# candle_circuit.net
KiCad netlist of a schematic drawn in EAGLE
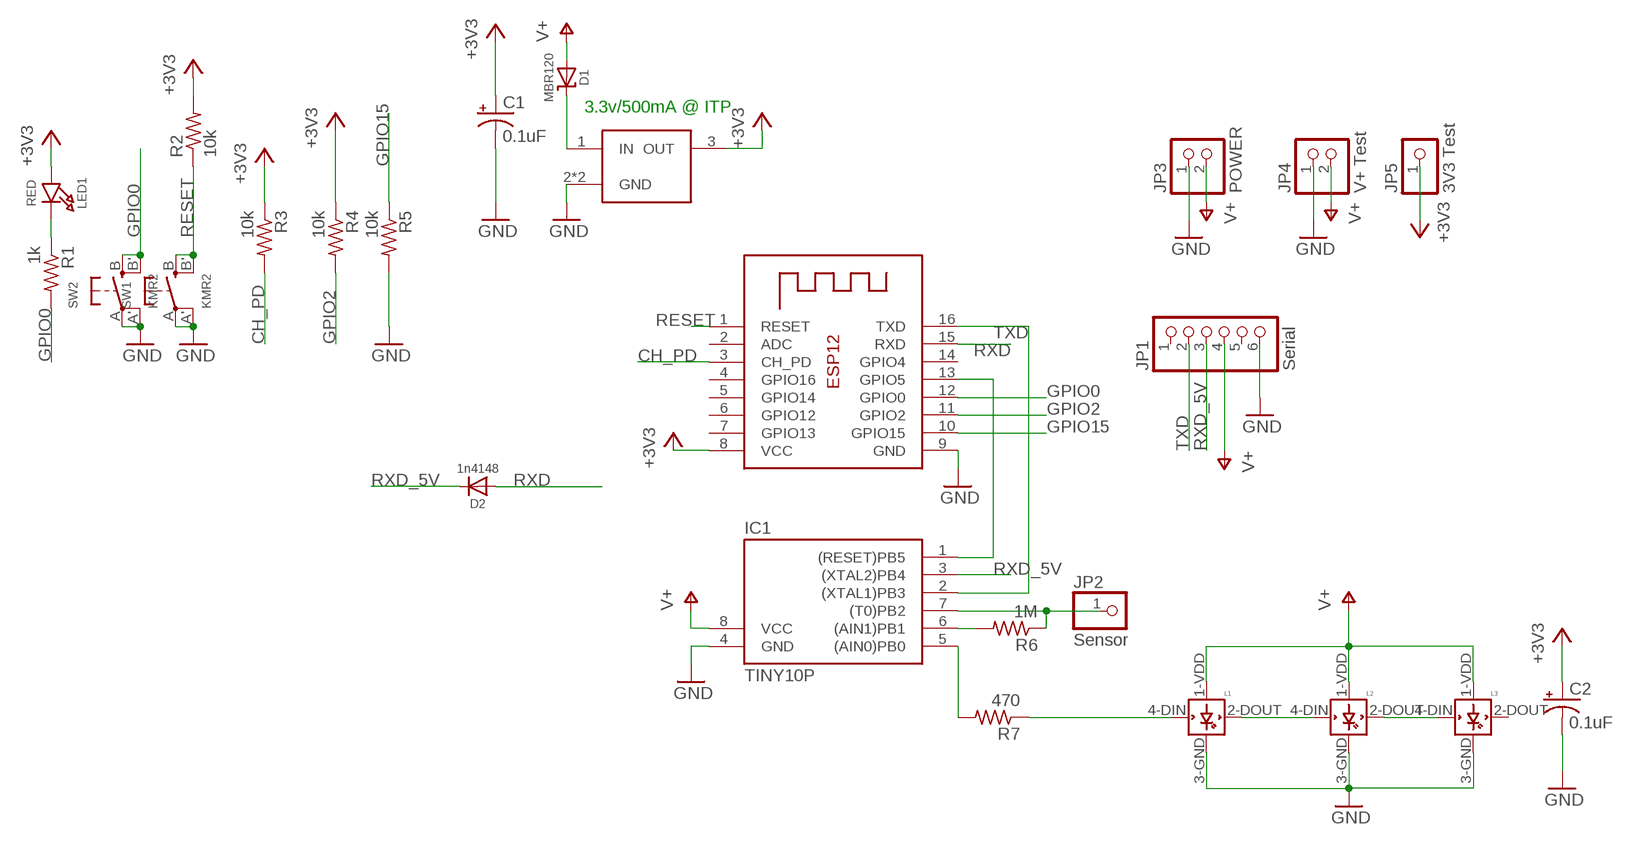
[diagram p0: schematic, sheet 1]

(export (version "E")
  (design (tool "Eeschema 10.0.6"))
  (components
    (comp (ref "C1")
      (value "0.1uF")
      (footprint "eagle-import:PANASONIC_C")
      (libsource (lib "eagle-import") (part "CAP_POLC"))
    )
    (comp (ref "C2")
      (value "0.1uF")
      (footprint "eagle-import:PANASONIC_C")
      (libsource (lib "eagle-import") (part "CAP_POLC"))
    )
    (comp (ref "D1")
      (value "MBR120")
      (footprint "eagle-import:SOD-123")
      (libsource (lib "eagle-import") (part "DIODE-SCHOTTKYSOD-123"))
    )
    (comp (ref "D2")
      (value "1n4148")
      (footprint "eagle-import:SOD-323")
      (libsource (lib "eagle-import") (part "DIODESOD-323"))
    )
    (comp (ref "IC1")
      (value "TINY10P")
      (footprint "eagle-import:DIL08")
      (libsource (lib "eagle-import") (part "TINY10P"))
    )
    (comp (ref "IC2")
      (value "ESP-12")
      (footprint "eagle-import:ESP-12")
      (libsource (lib "eagle-import") (part "ESP-12"))
    )
    (comp (ref "JP1")
      (value "Serial")
      (footprint "eagle-import:1X06_OVAL")
      (libsource (lib "eagle-import") (part "HEADER-1X6"))
    )
    (comp (ref "JP2")
      (value "Sensor")
      (footprint "eagle-import:1X01")
      (libsource (lib "eagle-import") (part "PINHD-1X1"))
    )
    (comp (ref "JP3")
      (value "POWER")
      (footprint "eagle-import:1X02_OVAL")
      (libsource (lib "eagle-import") (part "HEADER-1X2"))
    )
    (comp (ref "JP4")
      (value "V+ Test")
      (footprint "eagle-import:1X02_OVAL")
      (libsource (lib "eagle-import") (part "HEADER-1X2"))
    )
    (comp (ref "JP5")
      (value "3V3 Test")
      (footprint "eagle-import:1X01")
      (libsource (lib "eagle-import") (part "PINHD-1X1"))
    )
    (comp (ref "L1")
      (value "WS2812B")
      (footprint "eagle-import:WS2812B")
      (libsource (lib "eagle-import") (part "WS2812B"))
    )
    (comp (ref "L2")
      (value "WS2812B")
      (footprint "eagle-import:WS2812B")
      (libsource (lib "eagle-import") (part "WS2812B"))
    )
    (comp (ref "L3")
      (value "WS2812B")
      (footprint "eagle-import:WS2812B")
      (libsource (lib "eagle-import") (part "WS2812B"))
    )
    (comp (ref "LED1")
      (value "RED")
      (footprint "eagle-import:CHIPLED_0805_NOOUTLINE")
      (libsource (lib "eagle-import") (part "LED0805_NOOUTLINE"))
    )
    (comp (ref "R1")
      (value "1k")
      (footprint "eagle-import:R0603")
      (libsource (lib "eagle-import") (part "R-US_R0603"))
    )
    (comp (ref "R2")
      (value "10k")
      (footprint "eagle-import:R0603")
      (libsource (lib "eagle-import") (part "R-US_R0603"))
    )
    (comp (ref "R3")
      (value "10k")
      (footprint "eagle-import:R0603")
      (libsource (lib "eagle-import") (part "R-US_R0603"))
    )
    (comp (ref "R4")
      (value "10k")
      (footprint "eagle-import:R0603")
      (libsource (lib "eagle-import") (part "R-US_R0603"))
    )
    (comp (ref "R5")
      (value "10k")
      (footprint "eagle-import:R0603")
      (libsource (lib "eagle-import") (part "R-US_R0603"))
    )
    (comp (ref "R6")
      (value "1M")
      (footprint "eagle-import:R0603")
      (libsource (lib "eagle-import") (part "R-US_R0603"))
    )
    (comp (ref "R7")
      (value "470")
      (footprint "eagle-import:R0603")
      (libsource (lib "eagle-import") (part "R-US_R0603"))
    )
    (comp (ref "SW1")
      (value "KMR2")
      (footprint "eagle-import:BTN_KMR2_4.6X2.8")
      (libsource (lib "eagle-import") (part "SWITCH_TACT_SMT4.6X2.8"))
    )
    (comp (ref "SW2")
      (value "KMR2")
      (footprint "eagle-import:BTN_KMR2_4.6X2.8")
      (libsource (lib "eagle-import") (part "SWITCH_TACT_SMT4.6X2.8"))
    )
    (comp (ref "U1")
      (value "REGULATOR3.3V-UA78M33CDCYR")
      (footprint "eagle-import:SOT223")
      (libsource (lib "eagle-import") (part "REGULATOR3.3V-UA78M33CDCYR"))
    )
  )
  (nets
    (net (code "1") (name "+3V3") (class "Default")
      (node (ref "C1") (pin "+") (pinfunction "+_+") (pintype "passive"))
      (node (ref "C2") (pin "+") (pinfunction "+_+") (pintype "passive"))
      (node (ref "IC2") (pin "8") (pinfunction "VCC_8") (pintype "power_in"))
      (node (ref "JP5") (pin "1") (pinfunction "1_1") (pintype "passive"))
      (node (ref "LED1") (pin "A") (pinfunction "A_A") (pintype "passive"))
      (node (ref "R2") (pin "2") (pinfunction "2_2") (pintype "passive"))
      (node (ref "R3") (pin "1") (pinfunction "1_1") (pintype "passive"))
      (node (ref "R4") (pin "1") (pinfunction "1_1") (pintype "passive"))
      (node (ref "U1") (pin "3") (pinfunction "OUT_3") (pintype "bidirectional"))
    )
    (net (code "2") (name "/CH_PD") (class "Default")
      (node (ref "IC2") (pin "3") (pinfunction "CH_PD_3") (pintype "input"))
      (node (ref "R3") (pin "2") (pinfunction "2_2") (pintype "passive"))
    )
    (net (code "3") (name "/GPIO0") (class "Default")
      (node (ref "IC2") (pin "12") (pinfunction "GPIO0_12") (pintype "bidirectional"))
      (node (ref "R1") (pin "2") (pinfunction "2_2") (pintype "passive"))
      (node (ref "SW2") (pin "B") (pinfunction "S_B") (pintype "passive"))
      (node (ref "SW2") (pin "B'") (pinfunction "S1_B'") (pintype "passive"))
    )
    (net (code "4") (name "/GPIO2") (class "Default")
      (node (ref "IC2") (pin "11") (pinfunction "GPIO2_11") (pintype "bidirectional"))
      (node (ref "R4") (pin "2") (pinfunction "2_2") (pintype "passive"))
    )
    (net (code "5") (name "/GPIO15") (class "Default")
      (node (ref "IC2") (pin "10") (pinfunction "GPIO15_10") (pintype "bidirectional"))
      (node (ref "R5") (pin "1") (pinfunction "1_1") (pintype "passive"))
    )
    (net (code "6") (name "/RESET") (class "Default")
      (node (ref "IC2") (pin "1") (pinfunction "RESET_1") (pintype "input"))
      (node (ref "R2") (pin "1") (pinfunction "1_1") (pintype "passive"))
      (node (ref "SW1") (pin "B") (pinfunction "S_B") (pintype "passive"))
      (node (ref "SW1") (pin "B'") (pinfunction "S1_B'") (pintype "passive"))
    )
    (net (code "7") (name "/RXD") (class "Default")
      (node (ref "D2") (pin "A") (pinfunction "A_A") (pintype "passive"))
      (node (ref "IC2") (pin "15") (pinfunction "RXD_15") (pintype "input"))
    )
    (net (code "8") (name "/RXD_5V") (class "Default")
      (node (ref "D2") (pin "C") (pinfunction "C_C") (pintype "passive"))
      (node (ref "IC1") (pin "3") (pinfunction "(XTAL2)PB4_3") (pintype "bidirectional"))
      (node (ref "JP1") (pin "3") (pinfunction "3_3") (pintype "passive"))
    )
    (net (code "9") (name "/TXD") (class "Default")
      (node (ref "IC1") (pin "2") (pinfunction "(XTAL1)PB3_2") (pintype "bidirectional"))
      (node (ref "IC2") (pin "16") (pinfunction "TXD_16") (pintype "output"))
      (node (ref "JP1") (pin "2") (pinfunction "2_2") (pintype "passive"))
    )
    (net (code "10") (name "GND") (class "Default")
      (node (ref "C1") (pin "-") (pinfunction "-_-") (pintype "passive"))
      (node (ref "C2") (pin "-") (pinfunction "-_-") (pintype "passive"))
      (node (ref "IC1") (pin "4") (pinfunction "GND_4") (pintype "power_in"))
      (node (ref "IC2") (pin "9") (pinfunction "GND_9") (pintype "power_in"))
      (node (ref "JP1") (pin "6") (pinfunction "6_6") (pintype "passive"))
      (node (ref "JP3") (pin "1") (pinfunction "1_1") (pintype "passive"))
      (node (ref "JP4") (pin "1") (pinfunction "1_1") (pintype "passive"))
      (node (ref "L1") (pin "3-GND") (pinfunction "GND_3-GND") (pintype "bidirectional"))
      (node (ref "L2") (pin "3-GND") (pinfunction "GND_3-GND") (pintype "bidirectional"))
      (node (ref "L3") (pin "3-GND") (pinfunction "GND_3-GND") (pintype "bidirectional"))
      (node (ref "R5") (pin "2") (pinfunction "2_2") (pintype "passive"))
      (node (ref "SW1") (pin "A") (pinfunction "P_A") (pintype "passive"))
      (node (ref "SW1") (pin "A'") (pinfunction "P1_A'") (pintype "passive"))
      (node (ref "SW2") (pin "A") (pinfunction "P_A") (pintype "passive"))
      (node (ref "SW2") (pin "A'") (pinfunction "P1_A'") (pintype "passive"))
      (node (ref "U1") (pin "2") (pinfunction "GND_2") (pintype "bidirectional"))
      (node (ref "U1") (pin "4") (pinfunction "GND_4") (pintype "bidirectional"))
    )
    (net (code "11") (name "Net-(IC1-(AIN0)PB0)") (class "Default")
      (node (ref "IC1") (pin "5") (pinfunction "(AIN0)PB0_5") (pintype "bidirectional"))
      (node (ref "R7") (pin "2") (pinfunction "2_2") (pintype "passive"))
    )
    (net (code "12") (name "Net-(IC1-(AIN1)PB1)") (class "Default")
      (node (ref "IC1") (pin "6") (pinfunction "(AIN1)PB1_6") (pintype "bidirectional"))
      (node (ref "R6") (pin "2") (pinfunction "2_2") (pintype "passive"))
    )
    (net (code "13") (name "Net-(IC1-(RESET)PB5)") (class "Default")
      (node (ref "IC1") (pin "1") (pinfunction "(RESET)PB5_1") (pintype "bidirectional"))
      (node (ref "IC2") (pin "13") (pinfunction "GPIO5_13") (pintype "bidirectional"))
    )
    (net (code "14") (name "Net-(IC1-(T0)PB2)") (class "Default")
      (node (ref "IC1") (pin "7") (pinfunction "(T0)PB2_7") (pintype "bidirectional"))
      (node (ref "JP2") (pin "1") (pinfunction "1_1") (pintype "passive"))
      (node (ref "R6") (pin "1") (pinfunction "1_1") (pintype "passive"))
    )
    (net (code "15") (name "Net-(L1-DIN)") (class "Default")
      (node (ref "L1") (pin "4-DIN") (pinfunction "DIN_4-DIN") (pintype "input"))
      (node (ref "R7") (pin "1") (pinfunction "1_1") (pintype "passive"))
    )
    (net (code "16") (name "Net-(L1-DOUT)") (class "Default")
      (node (ref "L1") (pin "2-DOUT") (pinfunction "DOUT_2-DOUT") (pintype "output"))
      (node (ref "L2") (pin "4-DIN") (pinfunction "DIN_4-DIN") (pintype "input"))
    )
    (net (code "17") (name "Net-(L2-DOUT)") (class "Default")
      (node (ref "L2") (pin "2-DOUT") (pinfunction "DOUT_2-DOUT") (pintype "output"))
      (node (ref "L3") (pin "4-DIN") (pinfunction "DIN_4-DIN") (pintype "input"))
    )
    (net (code "18") (name "Net-(LED1-PadC)") (class "Default")
      (node (ref "LED1") (pin "C") (pinfunction "C_C") (pintype "passive"))
      (node (ref "R1") (pin "1") (pinfunction "1_1") (pintype "passive"))
    )
    (net (code "19") (name "Net-(U1-IN)") (class "Default")
      (node (ref "D1") (pin "C") (pinfunction "C_C") (pintype "passive"))
      (node (ref "U1") (pin "1") (pinfunction "IN_1") (pintype "bidirectional"))
    )
    (net (code "20") (name "V+") (class "Default")
      (node (ref "D1") (pin "A") (pinfunction "A_A") (pintype "passive"))
      (node (ref "IC1") (pin "8") (pinfunction "VCC_8") (pintype "power_in"))
      (node (ref "JP1") (pin "4") (pinfunction "4_4") (pintype "passive"))
      (node (ref "JP3") (pin "2") (pinfunction "2_2") (pintype "passive"))
      (node (ref "JP4") (pin "2") (pinfunction "2_2") (pintype "passive"))
      (node (ref "L1") (pin "1-VDD") (pinfunction "VDD_1-VDD") (pintype "bidirectional"))
      (node (ref "L2") (pin "1-VDD") (pinfunction "VDD_1-VDD") (pintype "bidirectional"))
      (node (ref "L3") (pin "1-VDD") (pinfunction "VDD_1-VDD") (pintype "bidirectional"))
    )
    (net (code "21") (name "unconnected-(IC2-ADC-Pad2)") (class "Default")
      (node (ref "IC2") (pin "2") (pinfunction "ADC_2") (pintype "passive"))
    )
    (net (code "22") (name "unconnected-(IC2-GPIO4-Pad14)") (class "Default")
      (node (ref "IC2") (pin "14") (pinfunction "GPIO4_14") (pintype "bidirectional"))
    )
    (net (code "23") (name "unconnected-(IC2-GPIO12-Pad6)") (class "Default")
      (node (ref "IC2") (pin "6") (pinfunction "GPIO12_6") (pintype "bidirectional"))
    )
    (net (code "24") (name "unconnected-(IC2-GPIO13-Pad7)") (class "Default")
      (node (ref "IC2") (pin "7") (pinfunction "GPIO13_7") (pintype "bidirectional"))
    )
    (net (code "25") (name "unconnected-(IC2-GPIO14-Pad5)") (class "Default")
      (node (ref "IC2") (pin "5") (pinfunction "GPIO14_5") (pintype "bidirectional"))
    )
    (net (code "26") (name "unconnected-(IC2-GPIO16-Pad4)") (class "Default")
      (node (ref "IC2") (pin "4") (pinfunction "GPIO16_4") (pintype "bidirectional"))
    )
    (net (code "27") (name "unconnected-(JP1-Pad1)") (class "Default")
      (node (ref "JP1") (pin "1") (pinfunction "1_1") (pintype "passive"))
    )
    (net (code "28") (name "unconnected-(JP1-Pad5)") (class "Default")
      (node (ref "JP1") (pin "5") (pinfunction "5_5") (pintype "passive"))
    )
    (net (code "29") (name "unconnected-(L3-DOUT-Pad2-DOUT)") (class "Default")
      (node (ref "L3") (pin "2-DOUT") (pinfunction "DOUT_2-DOUT") (pintype "output"))
    )
  )
)
